# commutator-controller.net
KiCad netlist of a schematic drawn in EAGLE
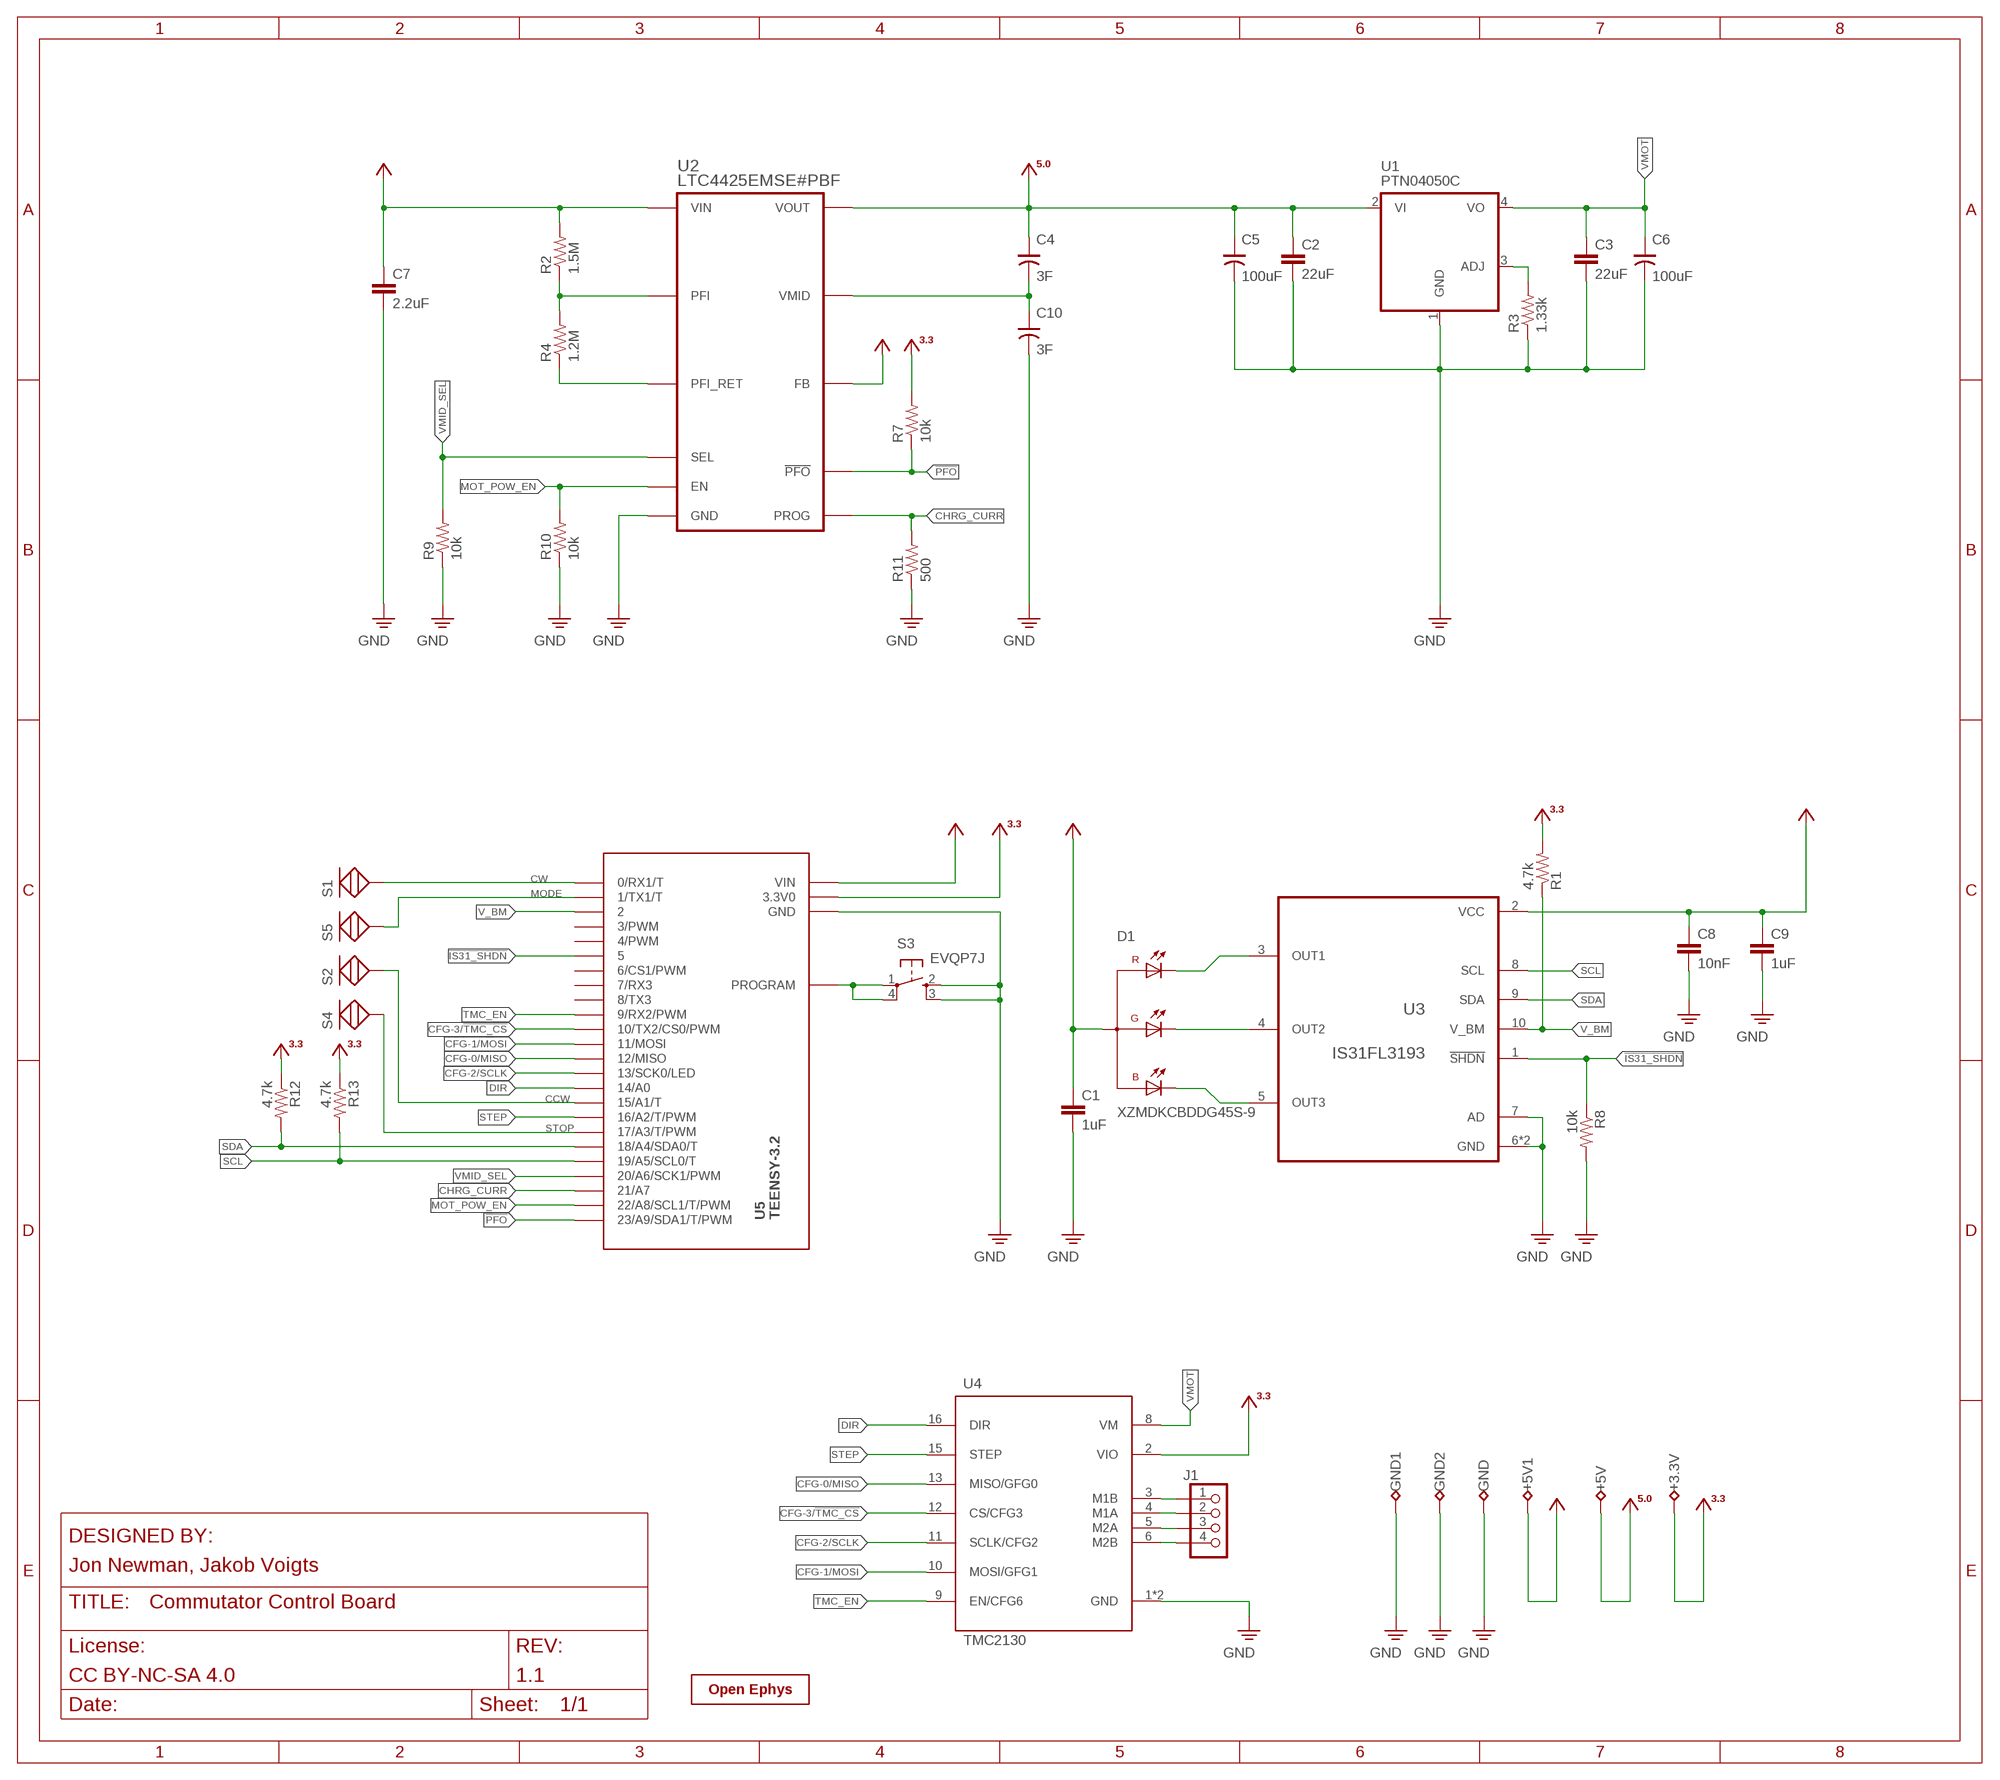
[diagram p0: schematic, sheet 1]

(export (version "E")
  (design (tool "Eeschema 10.0.6"))
  (components
    (comp (ref "+3.3V")
      (value "TPB2,54")
      (footprint "eagle-import:B2,54")
      (libsource (lib "eagle-import") (part "TPB2,54"))
    )
    (comp (ref "+5V")
      (value "TPB2,54")
      (footprint "eagle-import:B2,54")
      (libsource (lib "eagle-import") (part "TPB2,54"))
    )
    (comp (ref "+5V1")
      (value "TPB2,54")
      (footprint "eagle-import:B2,54")
      (libsource (lib "eagle-import") (part "TPB2,54"))
    )
    (comp (ref "C1")
      (value "1uF")
      (footprint "eagle-import:0603")
      (libsource (lib "eagle-import") (part "C_0603"))
    )
    (comp (ref "C2")
      (value "22uF")
      (footprint "eagle-import:1206")
      (libsource (lib "eagle-import") (part "C_1206"))
    )
    (comp (ref "C3")
      (value "22uF")
      (footprint "eagle-import:1206")
      (libsource (lib "eagle-import") (part "C_1206"))
    )
    (comp (ref "C4")
      (value "3F")
      (footprint "eagle-import:1210-POL")
      (libsource (lib "eagle-import") (part "C-POL_1210"))
    )
    (comp (ref "C5")
      (value "100uF")
      (footprint "eagle-import:153CLV-0807")
      (libsource (lib "eagle-import") (part "C-POL_0807"))
    )
    (comp (ref "C6")
      (value "100uF")
      (footprint "eagle-import:153CLV-0807")
      (libsource (lib "eagle-import") (part "C-POL_0807"))
    )
    (comp (ref "C7")
      (value "2.2uF")
      (footprint "eagle-import:0805")
      (fields (field (name "PARTNO") "C2012X5R1Cxxxxxxx"))
      (libsource (lib "eagle-import") (part "C_0805"))
    )
    (comp (ref "C8")
      (value "10nF")
      (footprint "eagle-import:0603")
      (libsource (lib "eagle-import") (part "C_0603"))
    )
    (comp (ref "C9")
      (value "1uF")
      (footprint "eagle-import:0603")
      (libsource (lib "eagle-import") (part "C_0603"))
    )
    (comp (ref "C10")
      (value "3F")
      (footprint "eagle-import:1210-POL")
      (libsource (lib "eagle-import") (part "C-POL_1210"))
    )
    (comp (ref "D1")
      (value "XZMDKCBDDG45S-9")
      (footprint "eagle-import:PLCC-INVERTED-NOHOLE")
      (libsource (lib "eagle-import") (part "LED-RGB_PLCC-INVERTED-NOHOLE"))
    )
    (comp (ref "GND")
      (value "TPB2,54")
      (footprint "eagle-import:B2,54")
      (libsource (lib "eagle-import") (part "TPB2,54"))
    )
    (comp (ref "GND1")
      (value "TPB2,54")
      (footprint "eagle-import:B2,54")
      (libsource (lib "eagle-import") (part "TPB2,54"))
    )
    (comp (ref "GND2")
      (value "TPB2,54")
      (footprint "eagle-import:B2,54")
      (libsource (lib "eagle-import") (part "TPB2,54"))
    )
    (comp (ref "J1")
      (value "PINHD-1X4_SMD-0.1\"")
      (footprint "eagle-import:JP4_SMD")
      (libsource (lib "eagle-import") (part "PINHD-1X4_SMD-0.1{dblquote}"))
    )
    (comp (ref "R1")
      (value "4.7k")
      (footprint "eagle-import:0603")
      (fields (field (name "MPN") "ERJ-3EKFxxxxV"))
      (libsource (lib "eagle-import") (part "R_0603"))
    )
    (comp (ref "R2")
      (value "1.5M")
      (footprint "eagle-import:0603")
      (fields (field (name "MPN") "ERJ-3EKFxxxxV"))
      (libsource (lib "eagle-import") (part "R_0603"))
    )
    (comp (ref "R3")
      (value "1.33k")
      (footprint "eagle-import:0603")
      (fields (field (name "MPN") "ERJ-3EKFxxxxV"))
      (libsource (lib "eagle-import") (part "R_0603"))
    )
    (comp (ref "R4")
      (value "1.2M")
      (footprint "eagle-import:0603")
      (fields (field (name "MPN") "ERJ-3EKFxxxxV"))
      (libsource (lib "eagle-import") (part "R_0603"))
    )
    (comp (ref "R7")
      (value "10k")
      (footprint "eagle-import:0603")
      (fields (field (name "MPN") "ERJ-3EKFxxxxV"))
      (libsource (lib "eagle-import") (part "R_0603"))
    )
    (comp (ref "R8")
      (value "10k")
      (footprint "eagle-import:0603")
      (fields (field (name "MPN") "ERJ-3EKFxxxxV"))
      (libsource (lib "eagle-import") (part "R_0603"))
    )
    (comp (ref "R9")
      (value "10k")
      (footprint "eagle-import:0603")
      (fields (field (name "MPN") "ERJ-3EKFxxxxV"))
      (libsource (lib "eagle-import") (part "R_0603"))
    )
    (comp (ref "R10")
      (value "10k")
      (footprint "eagle-import:0603")
      (fields (field (name "MPN") "ERJ-3EKFxxxxV"))
      (libsource (lib "eagle-import") (part "R_0603"))
    )
    (comp (ref "R11")
      (value "500")
      (footprint "eagle-import:0603")
      (fields (field (name "MPN") "ERJ-3EKFxxxxV"))
      (libsource (lib "eagle-import") (part "R_0603"))
    )
    (comp (ref "R12")
      (value "4.7k")
      (footprint "eagle-import:0603")
      (fields (field (name "MPN") "ERJ-3EKFxxxxV"))
      (libsource (lib "eagle-import") (part "R_0603"))
    )
    (comp (ref "R13")
      (value "4.7k")
      (footprint "eagle-import:0603")
      (fields (field (name "MPN") "ERJ-3EKFxxxxV"))
      (libsource (lib "eagle-import") (part "R_0603"))
    )
    (comp (ref "S1")
      (value "TOUCH_1MM")
      (footprint "eagle-import:TOUCH-1MM")
      (libsource (lib "eagle-import") (part "TOUCH_1MM"))
    )
    (comp (ref "S2")
      (value "TOUCH_1MM")
      (footprint "eagle-import:TOUCH-1MM")
      (libsource (lib "eagle-import") (part "TOUCH_1MM"))
    )
    (comp (ref "S3")
      (value "EVQP7J")
      (footprint "eagle-import:EVQP7")
      (libsource (lib "eagle-import") (part "SPST_TACT_EVQP7"))
    )
    (comp (ref "S4")
      (value "TOUCH_1MM")
      (footprint "eagle-import:TOUCH-1MM")
      (libsource (lib "eagle-import") (part "TOUCH_1MM"))
    )
    (comp (ref "S5")
      (value "TOUCH_1MM")
      (footprint "eagle-import:TOUCH-1MM")
      (libsource (lib "eagle-import") (part "TOUCH_1MM"))
    )
    (comp (ref "U1")
      (value "PTN04050C")
      (footprint "eagle-import:PDSS-B4-MODULE")
      (libsource (lib "eagle-import") (part "VREG_ADJ_R-PDSS-B4"))
    )
    (comp (ref "U2")
      (value "LTC4425EMSE#PBF")
      (footprint "eagle-import:MSOP-12-PAD")
      (libsource (lib "eagle-import") (part "LTC4425_MSOP"))
    )
    (comp (ref "U3")
      (value "IS31FL3193")
      (footprint "eagle-import:PWSON-N10-3X3")
      (libsource (lib "eagle-import") (part "IS31FL3193"))
    )
    (comp (ref "U4")
      (value "TMC2130")
      (footprint "eagle-import:SILENT-STEPPER-STICK-SMD")
      (libsource (lib "eagle-import") (part "SILENT-STEPPER-STICK-TMC2130_SMD"))
    )
    (comp (ref "U5")
      (value "TEENSY-3.2")
      (footprint "eagle-import:TEENSY_LC_SMD")
      (libsource (lib "eagle-import") (part "TEENSY_LC_SMD"))
    )
    (comp (ref "X1")
      (value "OE-LOGO_7X5")
      (footprint "eagle-import:OE-LOGO-7X5")
      (libsource (lib "eagle-import") (part "OE-LOGO_7X5"))
    )
  )
  (nets
    (net (code "1") (name "+3V3") (class "Default")
      (node (ref "+3.3V") (pin "TP") (pinfunction "TP_TP") (pintype "bidirectional"))
      (node (ref "R1") (pin "2") (pinfunction "2_2") (pintype "passive"))
      (node (ref "R12") (pin "1") (pinfunction "1_1") (pintype "passive"))
      (node (ref "R13") (pin "1") (pinfunction "1_1") (pintype "passive"))
      (node (ref "R7") (pin "2") (pinfunction "2_2") (pintype "passive"))
      (node (ref "U4") (pin "2") (pinfunction "VIO_2") (pintype "power_in"))
      (node (ref "U5") (pin "3.3") (pinfunction "3.3V0_3.3") (pintype "power_in"))
      (node (ref "U5") (pin "3V3") (pinfunction "3.3V0_3V3") (pintype "power_in"))
    )
    (net (code "2") (name "+5V") (class "Default")
      (node (ref "+5V") (pin "TP") (pinfunction "TP_TP") (pintype "bidirectional"))
      (node (ref "C2") (pin "1") (pinfunction "1_1") (pintype "passive"))
      (node (ref "C4") (pin "+") (pinfunction "+_+") (pintype "passive"))
      (node (ref "C5") (pin "+") (pinfunction "+_+") (pintype "passive"))
      (node (ref "U1") (pin "2") (pinfunction "VI_2") (pintype "power_in"))
      (node (ref "U2") (pin "1") (pinfunction "VOUT_1") (pintype "power_in"))
      (node (ref "U2") (pin "2") (pinfunction "VOUT_2") (pintype "power_in"))
    )
    (net (code "3") (name "/CCW") (class "Default")
      (node (ref "S2") (pin "PAD") (pinfunction "1_PAD") (pintype "passive"))
      (node (ref "U5") (pin "15") (pinfunction "15/A1/T_15") (pintype "bidirectional"))
    )
    (net (code "4") (name "/CFG-3{slash}~{TMC_CS}") (class "Default")
      (node (ref "U4") (pin "12") (pinfunction "CS/CFG3_12") (pintype "input"))
      (node (ref "U5") (pin "10") (pinfunction "10/TX2/CS0/PWM_10") (pintype "bidirectional"))
    )
    (net (code "5") (name "/CW") (class "Default")
      (node (ref "S1") (pin "PAD") (pinfunction "1_PAD") (pintype "passive"))
      (node (ref "U5") (pin "0") (pinfunction "0/RX1/T_0") (pintype "bidirectional"))
    )
    (net (code "6") (name "/MODE") (class "Default")
      (node (ref "S5") (pin "PAD") (pinfunction "1_PAD") (pintype "passive"))
      (node (ref "U5") (pin "1") (pinfunction "1/TX1/T_1") (pintype "bidirectional"))
    )
    (net (code "7") (name "/STOP") (class "Default")
      (node (ref "S4") (pin "PAD") (pinfunction "1_PAD") (pintype "passive"))
      (node (ref "U5") (pin "17") (pinfunction "17/A3/T/PWM_17") (pintype "bidirectional"))
    )
    (net (code "8") (name "/~{IS31_SHDN}") (class "Default")
      (node (ref "R8") (pin "1") (pinfunction "1_1") (pintype "passive"))
      (node (ref "U3") (pin "1") (pinfunction "~{SHDN}_1") (pintype "input"))
      (node (ref "U5") (pin "5") (pinfunction "5_5") (pintype "bidirectional"))
    )
    (net (code "9") (name "/~{PFO}") (class "Default")
      (node (ref "R7") (pin "1") (pinfunction "1_1") (pintype "passive"))
      (node (ref "U2") (pin "8") (pinfunction "~{PFO}_8") (pintype "input"))
      (node (ref "U5") (pin "23") (pinfunction "23/A9/SDA1/T/PWM_23") (pintype "bidirectional"))
    )
    (net (code "10") (name "CFG-0{slash}MISO") (class "Default")
      (node (ref "U4") (pin "13") (pinfunction "MISO/GFG0_13") (pintype "input"))
      (node (ref "U5") (pin "12") (pinfunction "12/MISO_12") (pintype "bidirectional"))
    )
    (net (code "11") (name "CFG-1{slash}MOSI") (class "Default")
      (node (ref "U4") (pin "10") (pinfunction "MOSI/GFG1_10") (pintype "input"))
      (node (ref "U5") (pin "11") (pinfunction "11/MOSI_11") (pintype "bidirectional"))
    )
    (net (code "12") (name "CFG-2{slash}SCLK") (class "Default")
      (node (ref "U4") (pin "11") (pinfunction "SCLK/CFG2_11") (pintype "input"))
      (node (ref "U5") (pin "13") (pinfunction "13/SCK0/LED_13") (pintype "bidirectional"))
    )
    (net (code "13") (name "CHRG_CURR") (class "Default")
      (node (ref "R11") (pin "2") (pinfunction "2_2") (pintype "passive"))
      (node (ref "U2") (pin "3") (pinfunction "PROG_3") (pintype "output"))
      (node (ref "U5") (pin "21") (pinfunction "21/A7_21") (pintype "bidirectional"))
    )
    (net (code "14") (name "DIR") (class "Default")
      (node (ref "U4") (pin "16") (pinfunction "DIR_16") (pintype "input"))
      (node (ref "U5") (pin "14") (pinfunction "14/A0_14") (pintype "bidirectional"))
    )
    (net (code "15") (name "GND") (class "Default")
      (node (ref "C1") (pin "2") (pinfunction "2_2") (pintype "passive"))
      (node (ref "C10") (pin "-") (pinfunction "-_-") (pintype "passive"))
      (node (ref "C2") (pin "2") (pinfunction "2_2") (pintype "passive"))
      (node (ref "C3") (pin "2") (pinfunction "2_2") (pintype "passive"))
      (node (ref "C5") (pin "-") (pinfunction "-_-") (pintype "passive"))
      (node (ref "C6") (pin "-") (pinfunction "-_-") (pintype "passive"))
      (node (ref "C7") (pin "2") (pinfunction "2_2") (pintype "passive"))
      (node (ref "C8") (pin "2") (pinfunction "2_2") (pintype "passive"))
      (node (ref "C9") (pin "2") (pinfunction "2_2") (pintype "passive"))
      (node (ref "GND") (pin "TP") (pinfunction "TP_TP") (pintype "bidirectional"))
      (node (ref "GND1") (pin "TP") (pinfunction "TP_TP") (pintype "bidirectional"))
      (node (ref "GND2") (pin "TP") (pinfunction "TP_TP") (pintype "bidirectional"))
      (node (ref "R10") (pin "1") (pinfunction "1_1") (pintype "passive"))
      (node (ref "R11") (pin "1") (pinfunction "1_1") (pintype "passive"))
      (node (ref "R3") (pin "1") (pinfunction "1_1") (pintype "passive"))
      (node (ref "R8") (pin "2") (pinfunction "2_2") (pintype "passive"))
      (node (ref "R9") (pin "1") (pinfunction "1_1") (pintype "passive"))
      (node (ref "S3") (pin "2") (pinfunction "S_2") (pintype "passive"))
      (node (ref "S3") (pin "3") (pinfunction "S1_3") (pintype "passive"))
      (node (ref "U1") (pin "1") (pinfunction "GND_1") (pintype "power_in"))
      (node (ref "U2") (pin "PAD") (pinfunction "GND_PAD") (pintype "power_in"))
      (node (ref "U3") (pin "6") (pinfunction "GND_6") (pintype "power_in"))
      (node (ref "U3") (pin "7") (pinfunction "AD_7") (pintype "input"))
      (node (ref "U3") (pin "PAD") (pinfunction "GND_PAD") (pintype "power_in"))
      (node (ref "U4") (pin "1") (pinfunction "GND_1") (pintype "power_in"))
      (node (ref "U4") (pin "7") (pinfunction "GND_7") (pintype "power_in"))
      (node (ref "U5") (pin "GND") (pinfunction "GND_GND") (pintype "power_in"))
      (node (ref "U5") (pin "GND1") (pinfunction "GND_GND1") (pintype "power_in"))
      (node (ref "U5") (pin "GND2") (pinfunction "GND_GND2") (pintype "power_in"))
    )
    (net (code "16") (name "MOT_POW_EN") (class "Default")
      (node (ref "R10") (pin "2") (pinfunction "2_2") (pintype "passive"))
      (node (ref "U2") (pin "6") (pinfunction "EN_6") (pintype "input"))
      (node (ref "U5") (pin "22") (pinfunction "22/A8/SCL1/T/PWM_22") (pintype "bidirectional"))
    )
    (net (code "17") (name "Net-(D1-CB)") (class "Default")
      (node (ref "D1") (pin "3") (pinfunction "CB_3") (pintype "passive"))
      (node (ref "U3") (pin "5") (pinfunction "OUT3_5") (pintype "open_collector"))
    )
    (net (code "18") (name "Net-(D1-CG)") (class "Default")
      (node (ref "D1") (pin "4") (pinfunction "CG_4") (pintype "passive"))
      (node (ref "U3") (pin "4") (pinfunction "OUT2_4") (pintype "open_collector"))
    )
    (net (code "19") (name "Net-(D1-CR)") (class "Default")
      (node (ref "D1") (pin "1") (pinfunction "CR_1") (pintype "passive"))
      (node (ref "U3") (pin "3") (pinfunction "OUT1_3") (pintype "open_collector"))
    )
    (net (code "20") (name "Net-(S3-P)") (class "Default")
      (node (ref "S3") (pin "1") (pinfunction "P_1") (pintype "passive"))
      (node (ref "S3") (pin "4") (pinfunction "P1_4") (pintype "passive"))
      (node (ref "U5") (pin "PROGRAM") (pinfunction "PROGRAM_PROGRAM") (pintype "power_in"))
    )
    (net (code "21") (name "Net-(U1-ADJ)") (class "Default")
      (node (ref "R3") (pin "2") (pinfunction "2_2") (pintype "passive"))
      (node (ref "U1") (pin "3") (pinfunction "ADJ_3") (pintype "input"))
    )
    (net (code "22") (name "Net-(U2-PFI)") (class "Default")
      (node (ref "R2") (pin "1") (pinfunction "1_1") (pintype "passive"))
      (node (ref "R4") (pin "2") (pinfunction "2_2") (pintype "passive"))
      (node (ref "U2") (pin "9") (pinfunction "PFI_9") (pintype "input"))
    )
    (net (code "23") (name "Net-(U2-PFI_RET)") (class "Default")
      (node (ref "R4") (pin "1") (pinfunction "1_1") (pintype "passive"))
      (node (ref "U2") (pin "7") (pinfunction "PFI_RET_7") (pintype "input"))
    )
    (net (code "24") (name "Net-(U2-VMID)") (class "Default")
      (node (ref "C10") (pin "+") (pinfunction "+_+") (pintype "passive"))
      (node (ref "C4") (pin "-") (pinfunction "-_-") (pintype "passive"))
      (node (ref "U2") (pin "10") (pinfunction "VMID_10") (pintype "input"))
    )
    (net (code "25") (name "Net-(U4-M1A)") (class "Default")
      (node (ref "J1") (pin "2") (pinfunction "2_2") (pintype "passive"))
      (node (ref "U4") (pin "4") (pinfunction "M1A_4") (pintype "output"))
    )
    (net (code "26") (name "Net-(U4-M1B)") (class "Default")
      (node (ref "J1") (pin "1") (pinfunction "1_1") (pintype "passive"))
      (node (ref "U4") (pin "3") (pinfunction "M1B_3") (pintype "output"))
    )
    (net (code "27") (name "Net-(U4-M2A)") (class "Default")
      (node (ref "J1") (pin "3") (pinfunction "3_3") (pintype "passive"))
      (node (ref "U4") (pin "5") (pinfunction "M2A_5") (pintype "output"))
    )
    (net (code "28") (name "Net-(U4-M2B)") (class "Default")
      (node (ref "J1") (pin "4") (pinfunction "4_4") (pintype "passive"))
      (node (ref "U4") (pin "6") (pinfunction "M2B_6") (pintype "output"))
    )
    (net (code "29") (name "SCL") (class "Default")
      (node (ref "R13") (pin "2") (pinfunction "2_2") (pintype "passive"))
      (node (ref "U3") (pin "8") (pinfunction "SCL_8") (pintype "input"))
      (node (ref "U5") (pin "19") (pinfunction "19/A5/SCL0/T_19") (pintype "bidirectional"))
    )
    (net (code "30") (name "SDA") (class "Default")
      (node (ref "R12") (pin "2") (pinfunction "2_2") (pintype "passive"))
      (node (ref "U3") (pin "9") (pinfunction "SDA_9") (pintype "input"))
      (node (ref "U5") (pin "18") (pinfunction "18/A4/SDA0/T_18") (pintype "bidirectional"))
    )
    (net (code "31") (name "STEP") (class "Default")
      (node (ref "U4") (pin "15") (pinfunction "STEP_15") (pintype "input"))
      (node (ref "U5") (pin "16") (pinfunction "16/A2/T/PWM_16") (pintype "bidirectional"))
    )
    (net (code "32") (name "TMC_EN") (class "Default")
      (node (ref "U4") (pin "9") (pinfunction "EN/CFG6_9") (pintype "input"))
      (node (ref "U5") (pin "9") (pinfunction "9/RX2/PWM_9") (pintype "bidirectional"))
    )
    (net (code "33") (name "VCC") (class "Default")
      (node (ref "+5V1") (pin "TP") (pinfunction "TP_TP") (pintype "bidirectional"))
      (node (ref "C1") (pin "1") (pinfunction "1_1") (pintype "passive"))
      (node (ref "C7") (pin "1") (pinfunction "1_1") (pintype "passive"))
      (node (ref "C8") (pin "1") (pinfunction "1_1") (pintype "passive"))
      (node (ref "C9") (pin "1") (pinfunction "1_1") (pintype "passive"))
      (node (ref "D1") (pin "2") (pinfunction "A_2") (pintype "passive"))
      (node (ref "R2") (pin "2") (pinfunction "2_2") (pintype "passive"))
      (node (ref "U2") (pin "11") (pinfunction "VIN_11") (pintype "power_in"))
      (node (ref "U2") (pin "12") (pinfunction "VIN_12") (pintype "power_in"))
      (node (ref "U2") (pin "5") (pinfunction "FB_5") (pintype "input"))
      (node (ref "U3") (pin "2") (pinfunction "VCC_2") (pintype "power_in"))
      (node (ref "U5") (pin "VIN") (pinfunction "VIN_VIN") (pintype "power_in"))
    )
    (net (code "34") (name "VMID_SEL") (class "Default")
      (node (ref "R9") (pin "2") (pinfunction "2_2") (pintype "passive"))
      (node (ref "U2") (pin "4") (pinfunction "SEL_4") (pintype "bidirectional"))
      (node (ref "U5") (pin "20") (pinfunction "20/A6/SCK1/PWM_20") (pintype "bidirectional"))
    )
    (net (code "35") (name "VMOT") (class "Default")
      (node (ref "C3") (pin "1") (pinfunction "1_1") (pintype "passive"))
      (node (ref "C6") (pin "+") (pinfunction "+_+") (pintype "passive"))
      (node (ref "U1") (pin "4") (pinfunction "VO_4") (pintype "power_in"))
      (node (ref "U4") (pin "8") (pinfunction "VM_8") (pintype "power_in"))
    )
    (net (code "36") (name "V_BM") (class "Default")
      (node (ref "R1") (pin "1") (pinfunction "1_1") (pintype "passive"))
      (node (ref "U3") (pin "10") (pinfunction "V_BM_10") (pintype "input"))
      (node (ref "U5") (pin "2") (pinfunction "2_2") (pintype "bidirectional"))
    )
    (net (code "37") (name "unconnected-(U5-3{slash}PWM-Pad3)") (class "Default")
      (node (ref "U5") (pin "3") (pinfunction "3/PWM_3") (pintype "bidirectional"))
    )
    (net (code "38") (name "unconnected-(U5-4{slash}PWM-Pad4)") (class "Default")
      (node (ref "U5") (pin "4") (pinfunction "4/PWM_4") (pintype "bidirectional"))
    )
    (net (code "39") (name "unconnected-(U5-6{slash}CS1{slash}PWM-Pad6)") (class "Default")
      (node (ref "U5") (pin "6") (pinfunction "6/CS1/PWM_6") (pintype "bidirectional"))
    )
    (net (code "40") (name "unconnected-(U5-7{slash}RX3-Pad7)") (class "Default")
      (node (ref "U5") (pin "7") (pinfunction "7/RX3_7") (pintype "bidirectional"))
    )
    (net (code "41") (name "unconnected-(U5-8{slash}TX3-Pad8)") (class "Default")
      (node (ref "U5") (pin "8") (pinfunction "8/TX3_8") (pintype "bidirectional"))
    )
  )
)
